# ADC1.net
KiCad netlist of a schematic drawn in Altium Designer
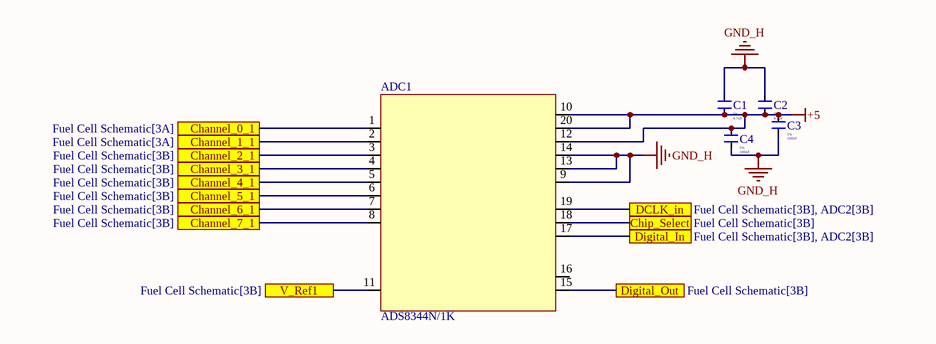
[diagram p0: ADC1.SchDoc]

(export (version "E")
  (design (tool "Eeschema 10.0.6"))
  (components
    (comp (ref "ADC1")
      (value "ADS8344N/1K")
      (footprint "ADS8344")
      (description "IC ADC 16BIT SAR 20SSOP")
      (fields (field (name "MANUFACTURER") "Texas Instruments"))
      (libsource (lib "Schlib1") (part "ADS8344N/1K"))
    )
    (comp (ref "C1")
      (value "~")
      (footprint "Capacitor_Kemet_0805")
      (description "CAP CER 4.7UF 16V X7R 0805")
      (fields
        (field (name "MANUFACTURER") "KEMET")
        (field (name "MANUFACTURER PART NUMBER") "C0805C475J4RACAUTO")
        (field (name "TOLERANCE") "5%")
        (field (name "CAPACITANCE") "4.7uF")
      )
      (libsource (lib "Schlib1") (part "C0805C475J4RACAUTO"))
    )
    (comp (ref "C2")
      (value "~")
      (footprint "Capacitor_Kemet_0805")
      (description "CAP CER 4.7UF 16V X7R 0805")
      (fields
        (field (name "MANUFACTURER") "KEMET")
        (field (name "MANUFACTURER PART NUMBER") "C0805C475J4RACAUTO")
        (field (name "TOLERANCE") "5%")
        (field (name "CAPACITANCE") "4.7uF")
      )
      (libsource (lib "Schlib1") (part "C0805C475J4RACAUTO"))
    )
    (comp (ref "C3")
      (value "~")
      (footprint "Capacitor_Kemet_0805")
      (description "Cap Ceramic 0.1uF 16V X7R 5% SMD 0805 125°C Plastic T/R")
      (fields
        (field (name "MANUFACTURER") "KEMET")
        (field (name "MANUFACTURER PART NUMBER") "C0805C104J4RACTU")
        (field (name "DISSIPATION FACTOR") "5%")
        (field (name "CAPACITANCE") "100nF")
      )
      (libsource (lib "Schlib1") (part "C0805C104J4RACTU"))
    )
    (comp (ref "C4")
      (value "~")
      (footprint "Capacitor_Kemet_0805")
      (description "Cap Ceramic 0.1uF 16V X7R 5% SMD 0805 125°C Plastic T/R")
      (fields
        (field (name "MANUFACTURER") "KEMET")
        (field (name "MANUFACTURER PART NUMBER") "C0805C104J4RACTU")
        (field (name "DISSIPATION FACTOR") "5%")
        (field (name "CAPACITANCE") "100nF")
      )
      (libsource (lib "Schlib1") (part "C0805C104J4RACTU"))
    )
  )
  (nets
    (net (code "1") (name "+5") (class "Default")
      (node (ref "ADC1") (pin "10") (pinfunction "Shutdown_10") (pintype "passive"))
      (node (ref "ADC1") (pin "12") (pinfunction "+VCC_12") (pintype "passive"))
      (node (ref "ADC1") (pin "20") (pinfunction "+VCC_20") (pintype "passive"))
      (node (ref "C1") (pin "1") (pinfunction "1_1") (pintype "passive"))
      (node (ref "C2") (pin "1") (pinfunction "1_1") (pintype "passive"))
      (node (ref "C3") (pin "2") (pinfunction "2_2") (pintype "passive"))
      (node (ref "C4") (pin "2") (pinfunction "2_2") (pintype "passive"))
    )
    (net (code "2") (name "/Channel_0_1") (class "Default")
      (node (ref "ADC1") (pin "1") (pinfunction "Channel_0_1") (pintype "passive"))
    )
    (net (code "3") (name "/Channel_1_1") (class "Default")
      (node (ref "ADC1") (pin "2") (pinfunction "Channel_1_2") (pintype "passive"))
    )
    (net (code "4") (name "/Channel_2_1") (class "Default")
      (node (ref "ADC1") (pin "3") (pinfunction "Channel_2_3") (pintype "passive"))
    )
    (net (code "5") (name "/Channel_3_1") (class "Default")
      (node (ref "ADC1") (pin "4") (pinfunction "Channel_3_4") (pintype "passive"))
    )
    (net (code "6") (name "/Channel_4_1") (class "Default")
      (node (ref "ADC1") (pin "5") (pinfunction "Channel_4_5") (pintype "passive"))
    )
    (net (code "7") (name "/Channel_5_1") (class "Default")
      (node (ref "ADC1") (pin "6") (pinfunction "Channel_5_6") (pintype "passive"))
    )
    (net (code "8") (name "/Channel_6_1") (class "Default")
      (node (ref "ADC1") (pin "7") (pinfunction "Channel_6_7") (pintype "passive"))
    )
    (net (code "9") (name "/Channel_7_1") (class "Default")
      (node (ref "ADC1") (pin "8") (pinfunction "Channel_7_8") (pintype "passive"))
    )
    (net (code "10") (name "/Chip_Select") (class "Default")
      (node (ref "ADC1") (pin "18") (pinfunction "Chip_Select_18") (pintype "passive"))
    )
    (net (code "11") (name "/DCLK_in") (class "Default")
      (node (ref "ADC1") (pin "19") (pinfunction "Digital_Clock_19") (pintype "passive"))
    )
    (net (code "12") (name "/Digital_In") (class "Default")
      (node (ref "ADC1") (pin "17") (pinfunction "Digital_In_17") (pintype "passive"))
    )
    (net (code "13") (name "/Digital_Out") (class "Default")
      (node (ref "ADC1") (pin "15") (pinfunction "Digital_Out_15") (pintype "passive"))
    )
    (net (code "14") (name "/V_Ref1") (class "Default")
      (node (ref "ADC1") (pin "11") (pinfunction "V_Reference_11") (pintype "passive"))
    )
    (net (code "15") (name "GND_H") (class "Default")
      (node (ref "ADC1") (pin "13") (pinfunction "Ground_13") (pintype "passive"))
      (node (ref "ADC1") (pin "14") (pinfunction "Ground_14") (pintype "passive"))
      (node (ref "ADC1") (pin "9") (pinfunction "Common_Reference_9") (pintype "passive"))
      (node (ref "C1") (pin "2") (pinfunction "2_2") (pintype "passive"))
      (node (ref "C2") (pin "2") (pinfunction "2_2") (pintype "passive"))
      (node (ref "C3") (pin "1") (pinfunction "1_1") (pintype "passive"))
      (node (ref "C4") (pin "1") (pinfunction "1_1") (pintype "passive"))
    )
    (net (code "16") (name "unconnected-(ADC1-Busy-Pad16)") (class "Default")
      (node (ref "ADC1") (pin "16") (pinfunction "Busy_16") (pintype "passive"))
    )
  )
)
